# POWER.net
KiCad netlist of a schematic drawn in Altium Designer
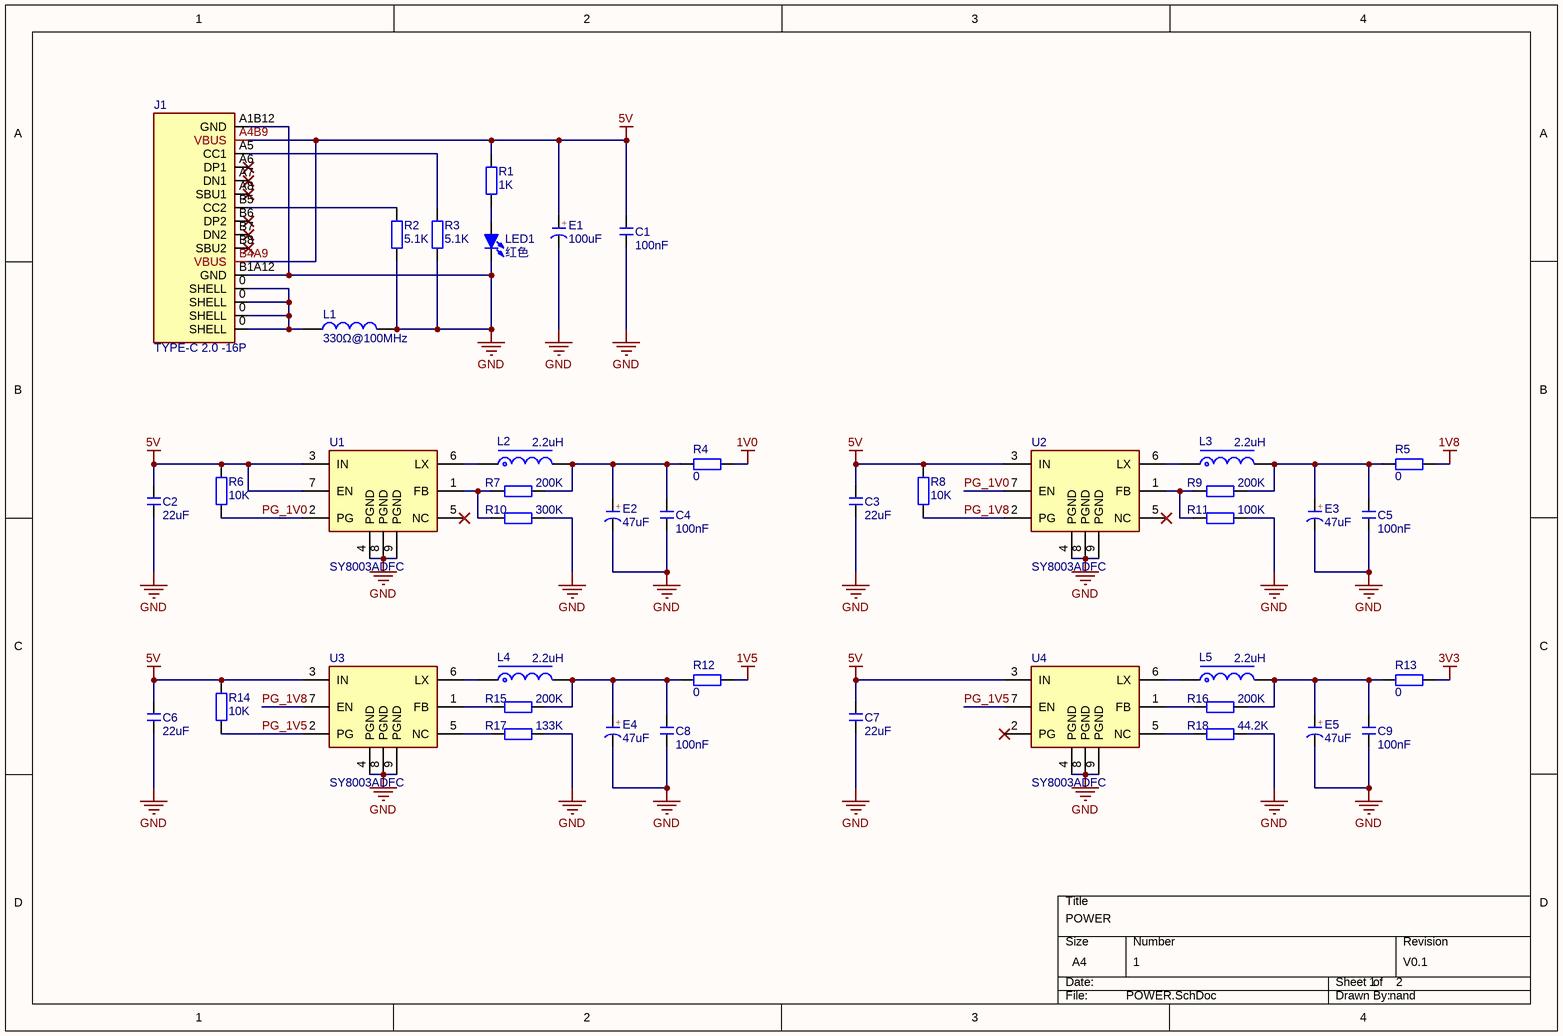
[diagram p0: POWER.SchDoc]

(export (version "E")
  (design (tool "Eeschema 10.0.6"))
  (components
    (comp (ref "C1")
      (value "100nF")
      (footprint "C 0402_L")
      (description "无极性贴片电容")
      (fields (field (name "版权归属") "源创客"))
      (libsource (lib "3.1   - 电阻-电容-电感") (part "C"))
    )
    (comp (ref "C2")
      (value "22uF")
      (footprint "C 0805_L")
      (description "无极性贴片电容")
      (fields (field (name "版权归属") "源创客"))
      (libsource (lib "3.1   - 电阻-电容-电感") (part "C"))
    )
    (comp (ref "C3")
      (value "22uF")
      (footprint "C 0805_L")
      (description "无极性贴片电容")
      (fields (field (name "版权归属") "源创客"))
      (libsource (lib "3.1   - 电阻-电容-电感") (part "C"))
    )
    (comp (ref "C4")
      (value "100nF")
      (footprint "C 0402_L")
      (description "无极性贴片电容")
      (fields (field (name "版权归属") "源创客"))
      (libsource (lib "3.1   - 电阻-电容-电感") (part "C"))
    )
    (comp (ref "C5")
      (value "100nF")
      (footprint "C 0402_L")
      (description "无极性贴片电容")
      (fields (field (name "版权归属") "源创客"))
      (libsource (lib "3.1   - 电阻-电容-电感") (part "C"))
    )
    (comp (ref "C6")
      (value "22uF")
      (footprint "C 0805_L")
      (description "无极性贴片电容")
      (fields (field (name "版权归属") "源创客"))
      (libsource (lib "3.1   - 电阻-电容-电感") (part "C"))
    )
    (comp (ref "C7")
      (value "22uF")
      (footprint "C 0805_L")
      (description "无极性贴片电容")
      (fields (field (name "版权归属") "源创客"))
      (libsource (lib "3.1   - 电阻-电容-电感") (part "C"))
    )
    (comp (ref "C8")
      (value "100nF")
      (footprint "C 0402_L")
      (description "无极性贴片电容")
      (fields (field (name "版权归属") "源创客"))
      (libsource (lib "3.1   - 电阻-电容-电感") (part "C"))
    )
    (comp (ref "C9")
      (value "100nF")
      (footprint "C 0402_L")
      (description "无极性贴片电容")
      (fields (field (name "版权归属") "源创客"))
      (libsource (lib "3.1   - 电阻-电容-电感") (part "C"))
    )
    (comp (ref "E1")
      (value "100uF")
      (footprint "CD A(3216)")
      (description "贴片钽电容")
      (fields (field (name "版权归属") "源创客"))
      (libsource (lib "3.1   - 电阻-电容-电感") (part "C-CD"))
    )
    (comp (ref "E2")
      (value "47uF")
      (footprint "CD A(3216)")
      (description "贴片钽电容")
      (fields (field (name "版权归属") "源创客"))
      (libsource (lib "3.1   - 电阻-电容-电感") (part "C-CD"))
    )
    (comp (ref "E3")
      (value "47uF")
      (footprint "CD A(3216)")
      (description "贴片钽电容")
      (fields (field (name "版权归属") "源创客"))
      (libsource (lib "3.1   - 电阻-电容-电感") (part "C-CD"))
    )
    (comp (ref "E4")
      (value "47uF")
      (footprint "CD A(3216)")
      (description "贴片钽电容")
      (fields (field (name "版权归属") "源创客"))
      (libsource (lib "3.1   - 电阻-电容-电感") (part "C-CD"))
    )
    (comp (ref "E5")
      (value "47uF")
      (footprint "CD A(3216)")
      (description "贴片钽电容")
      (fields (field (name "版权归属") "源创客"))
      (libsource (lib "3.1   - 电阻-电容-电感") (part "C-CD"))
    )
    (comp (ref "J1")
      (value "TYPE-C 2.0 -16P")
      (footprint "USB-C-SMD_16P")
      (description "USB2.0_Type-C_16Pin母座")
      (libsource (lib "4.1   - 接口类") (part "USB2.0_Type-C_16Pin"))
    )
    (comp (ref "L1")
      (value "330Ω@100MHz")
      (footprint "L 0805")
      (description "小功率贴片电感")
      (fields (field (name "版权归属") "源创客"))
      (libsource (lib "3.1   - 电阻-电容-电感") (part "L"))
    )
    (comp (ref "L2")
      (value "2.2uH")
      (footprint "CD52")
      (description "贴片功率电感")
      (fields (field (name "版权归属") "源创客"))
      (libsource (lib "3.1   - 电阻-电容-电感") (part "L-CD"))
    )
    (comp (ref "L3")
      (value "2.2uH")
      (footprint "CD52")
      (description "贴片功率电感")
      (fields (field (name "版权归属") "源创客"))
      (libsource (lib "3.1   - 电阻-电容-电感") (part "L-CD"))
    )
    (comp (ref "L4")
      (value "2.2uH")
      (footprint "CD52")
      (description "贴片功率电感")
      (fields (field (name "版权归属") "源创客"))
      (libsource (lib "3.1   - 电阻-电容-电感") (part "L-CD"))
    )
    (comp (ref "L5")
      (value "2.2uH")
      (footprint "CD52")
      (description "贴片功率电感")
      (fields (field (name "版权归属") "源创客"))
      (libsource (lib "3.1   - 电阻-电容-电感") (part "L-CD"))
    )
    (comp (ref "LED1")
      (value "红色")
      (footprint "LED 0805G")
      (description "贴片LED")
      (fields (field (name "版权归属") "源创客"))
      (libsource (lib "9.1   - LED") (part "LED-SMD"))
    )
    (comp (ref "R1")
      (value "1K")
      (footprint "R 0402_L")
      (description "贴片电阻")
      (fields (field (name "版权归属") "源创客"))
      (libsource (lib "3.1   - 电阻-电容-电感") (part "R"))
    )
    (comp (ref "R2")
      (value "5.1K")
      (footprint "R 0402_L")
      (description "贴片电阻")
      (fields (field (name "版权归属") "源创客"))
      (libsource (lib "3.1   - 电阻-电容-电感") (part "R"))
    )
    (comp (ref "R3")
      (value "5.1K")
      (footprint "R 0402_L")
      (description "贴片电阻")
      (fields (field (name "版权归属") "源创客"))
      (libsource (lib "3.1   - 电阻-电容-电感") (part "R"))
    )
    (comp (ref "R4")
      (value "0")
      (footprint "R 0603_L")
      (description "贴片电阻")
      (fields (field (name "版权归属") "源创客"))
      (libsource (lib "3.1   - 电阻-电容-电感") (part "R"))
    )
    (comp (ref "R5")
      (value "0")
      (footprint "R 0603_L")
      (description "贴片电阻")
      (fields (field (name "版权归属") "源创客"))
      (libsource (lib "3.1   - 电阻-电容-电感") (part "R"))
    )
    (comp (ref "R6")
      (value "10K")
      (footprint "R 0402_L")
      (description "贴片电阻")
      (fields (field (name "版权归属") "源创客"))
      (libsource (lib "3.1   - 电阻-电容-电感") (part "R"))
    )
    (comp (ref "R7")
      (value "200K")
      (footprint "R 0805_L")
      (description "贴片电阻")
      (fields (field (name "版权归属") "源创客"))
      (libsource (lib "3.1   - 电阻-电容-电感") (part "R"))
    )
    (comp (ref "R8")
      (value "10K")
      (footprint "R 0402_L")
      (description "贴片电阻")
      (fields (field (name "版权归属") "源创客"))
      (libsource (lib "3.1   - 电阻-电容-电感") (part "R"))
    )
    (comp (ref "R9")
      (value "200K")
      (footprint "R 0805_L")
      (description "贴片电阻")
      (fields (field (name "版权归属") "源创客"))
      (libsource (lib "3.1   - 电阻-电容-电感") (part "R"))
    )
    (comp (ref "R10")
      (value "300K")
      (footprint "R 0805_L")
      (description "贴片电阻")
      (fields (field (name "版权归属") "源创客"))
      (libsource (lib "3.1   - 电阻-电容-电感") (part "R"))
    )
    (comp (ref "R11")
      (value "100K")
      (footprint "R 0805_L")
      (description "贴片电阻")
      (fields (field (name "版权归属") "源创客"))
      (libsource (lib "3.1   - 电阻-电容-电感") (part "R"))
    )
    (comp (ref "R12")
      (value "0")
      (footprint "R 0603_L")
      (description "贴片电阻")
      (fields (field (name "版权归属") "源创客"))
      (libsource (lib "3.1   - 电阻-电容-电感") (part "R"))
    )
    (comp (ref "R13")
      (value "0")
      (footprint "R 0603_L")
      (description "贴片电阻")
      (fields (field (name "版权归属") "源创客"))
      (libsource (lib "3.1   - 电阻-电容-电感") (part "R"))
    )
    (comp (ref "R14")
      (value "10K")
      (footprint "R 0402_L")
      (description "贴片电阻")
      (fields (field (name "版权归属") "源创客"))
      (libsource (lib "3.1   - 电阻-电容-电感") (part "R"))
    )
    (comp (ref "R15")
      (value "200K")
      (footprint "R 0805_L")
      (description "贴片电阻")
      (fields (field (name "版权归属") "源创客"))
      (libsource (lib "3.1   - 电阻-电容-电感") (part "R"))
    )
    (comp (ref "R16")
      (value "200K")
      (footprint "R 0805_L")
      (description "贴片电阻")
      (fields (field (name "版权归属") "源创客"))
      (libsource (lib "3.1   - 电阻-电容-电感") (part "R"))
    )
    (comp (ref "R17")
      (value "133K")
      (footprint "R 0805_L")
      (description "贴片电阻")
      (fields (field (name "版权归属") "源创客"))
      (libsource (lib "3.1   - 电阻-电容-电感") (part "R"))
    )
    (comp (ref "R18")
      (value "44.2K")
      (footprint "R 0805_L")
      (description "贴片电阻")
      (fields (field (name "版权归属") "源创客"))
      (libsource (lib "3.1   - 电阻-电容-电感") (part "R"))
    )
    (comp (ref "U1")
      (value "SY8003ADFC")
      (footprint "SON50P200X200X65-9N")
      (description "开关电源")
      (libsource (lib "1.1   - IC芯片") (part "SY8003ADFC"))
    )
    (comp (ref "U2")
      (value "SY8003ADFC")
      (footprint "SON50P200X200X65-9N")
      (description "开关电源")
      (libsource (lib "1.1   - IC芯片") (part "SY8003ADFC"))
    )
    (comp (ref "U3")
      (value "SY8003ADFC")
      (footprint "SON50P200X200X65-9N")
      (description "开关电源")
      (libsource (lib "1.1   - IC芯片") (part "SY8003ADFC"))
    )
    (comp (ref "U4")
      (value "SY8003ADFC")
      (footprint "SON50P200X200X65-9N")
      (description "开关电源")
      (libsource (lib "1.1   - IC芯片") (part "SY8003ADFC"))
    )
  )
  (nets
    (net (code "1") (name "/PG_1V0") (class "Default")
      (node (ref "R6") (pin "1") (pinfunction "1_1") (pintype "passive"))
      (node (ref "U1") (pin "2") (pinfunction "PG_2") (pintype "passive"))
      (node (ref "U2") (pin "7") (pinfunction "EN_7") (pintype "passive"))
    )
    (net (code "2") (name "/PG_1V5") (class "Default")
      (node (ref "R14") (pin "1") (pinfunction "1_1") (pintype "passive"))
      (node (ref "U3") (pin "2") (pinfunction "PG_2") (pintype "passive"))
      (node (ref "U4") (pin "7") (pinfunction "EN_7") (pintype "passive"))
    )
    (net (code "3") (name "/PG_1V8") (class "Default")
      (node (ref "R8") (pin "1") (pinfunction "1_1") (pintype "passive"))
      (node (ref "U2") (pin "2") (pinfunction "PG_2") (pintype "passive"))
      (node (ref "U3") (pin "7") (pinfunction "EN_7") (pintype "passive"))
    )
    (net (code "4") (name "1V0") (class "Default")
      (node (ref "R4") (pin "1") (pinfunction "1_1") (pintype "passive"))
    )
    (net (code "5") (name "1V5") (class "Default")
      (node (ref "R12") (pin "1") (pinfunction "1_1") (pintype "passive"))
    )
    (net (code "6") (name "1V8") (class "Default")
      (node (ref "R5") (pin "1") (pinfunction "1_1") (pintype "passive"))
    )
    (net (code "7") (name "3V3") (class "Default")
      (node (ref "R13") (pin "1") (pinfunction "1_1") (pintype "passive"))
    )
    (net (code "8") (name "5V") (class "Default")
      (node (ref "C1") (pin "2") (pinfunction "2_2") (pintype "passive"))
      (node (ref "C2") (pin "2") (pinfunction "2_2") (pintype "passive"))
      (node (ref "C3") (pin "2") (pinfunction "2_2") (pintype "passive"))
      (node (ref "C6") (pin "2") (pinfunction "2_2") (pintype "passive"))
      (node (ref "C7") (pin "2") (pinfunction "2_2") (pintype "passive"))
      (node (ref "E1") (pin "1") (pinfunction "A_1") (pintype "passive"))
      (node (ref "J1") (pin "A4B9") (pinfunction "VBUS_A4B9") (pintype "passive"))
      (node (ref "J1") (pin "B4A9") (pinfunction "VBUS_B4A9") (pintype "passive"))
      (node (ref "R1") (pin "2") (pinfunction "2_2") (pintype "passive"))
      (node (ref "R14") (pin "2") (pinfunction "2_2") (pintype "passive"))
      (node (ref "R6") (pin "2") (pinfunction "2_2") (pintype "passive"))
      (node (ref "R8") (pin "2") (pinfunction "2_2") (pintype "passive"))
      (node (ref "U1") (pin "3") (pinfunction "IN_3") (pintype "passive"))
      (node (ref "U1") (pin "7") (pinfunction "EN_7") (pintype "passive"))
      (node (ref "U2") (pin "3") (pinfunction "IN_3") (pintype "passive"))
      (node (ref "U3") (pin "3") (pinfunction "IN_3") (pintype "passive"))
      (node (ref "U4") (pin "3") (pinfunction "IN_3") (pintype "passive"))
    )
    (net (code "9") (name "GND") (class "Default")
      (node (ref "C1") (pin "1") (pinfunction "1_1") (pintype "passive"))
      (node (ref "C2") (pin "1") (pinfunction "1_1") (pintype "passive"))
      (node (ref "C3") (pin "1") (pinfunction "1_1") (pintype "passive"))
      (node (ref "C4") (pin "1") (pinfunction "1_1") (pintype "passive"))
      (node (ref "C5") (pin "1") (pinfunction "1_1") (pintype "passive"))
      (node (ref "C6") (pin "1") (pinfunction "1_1") (pintype "passive"))
      (node (ref "C7") (pin "1") (pinfunction "1_1") (pintype "passive"))
      (node (ref "C8") (pin "1") (pinfunction "1_1") (pintype "passive"))
      (node (ref "C9") (pin "1") (pinfunction "1_1") (pintype "passive"))
      (node (ref "E1") (pin "2") (pinfunction "K_2") (pintype "passive"))
      (node (ref "E2") (pin "2") (pinfunction "K_2") (pintype "passive"))
      (node (ref "E3") (pin "2") (pinfunction "K_2") (pintype "passive"))
      (node (ref "E4") (pin "2") (pinfunction "K_2") (pintype "passive"))
      (node (ref "E5") (pin "2") (pinfunction "K_2") (pintype "passive"))
      (node (ref "J1") (pin "A1B12") (pinfunction "GND_A1B12") (pintype "passive"))
      (node (ref "J1") (pin "B1A12") (pinfunction "GND_B1A12") (pintype "passive"))
      (node (ref "L1") (pin "2") (pinfunction "2_2") (pintype "passive"))
      (node (ref "LED1") (pin "2") (pinfunction "K_2") (pintype "passive"))
      (node (ref "R10") (pin "1") (pinfunction "1_1") (pintype "passive"))
      (node (ref "R11") (pin "1") (pinfunction "1_1") (pintype "passive"))
      (node (ref "R17") (pin "1") (pinfunction "1_1") (pintype "passive"))
      (node (ref "R18") (pin "1") (pinfunction "1_1") (pintype "passive"))
      (node (ref "R2") (pin "1") (pinfunction "1_1") (pintype "passive"))
      (node (ref "R3") (pin "1") (pinfunction "1_1") (pintype "passive"))
      (node (ref "U1") (pin "4") (pinfunction "PGND_4") (pintype "passive"))
      (node (ref "U1") (pin "8") (pinfunction "PGND_8") (pintype "passive"))
      (node (ref "U1") (pin "9") (pinfunction "PGND_9") (pintype "passive"))
      (node (ref "U2") (pin "4") (pinfunction "PGND_4") (pintype "passive"))
      (node (ref "U2") (pin "8") (pinfunction "PGND_8") (pintype "passive"))
      (node (ref "U2") (pin "9") (pinfunction "PGND_9") (pintype "passive"))
      (node (ref "U3") (pin "4") (pinfunction "PGND_4") (pintype "passive"))
      (node (ref "U3") (pin "8") (pinfunction "PGND_8") (pintype "passive"))
      (node (ref "U3") (pin "9") (pinfunction "PGND_9") (pintype "passive"))
      (node (ref "U4") (pin "4") (pinfunction "PGND_4") (pintype "passive"))
      (node (ref "U4") (pin "8") (pinfunction "PGND_8") (pintype "passive"))
      (node (ref "U4") (pin "9") (pinfunction "PGND_9") (pintype "passive"))
    )
    (net (code "10") (name "Net-(E2-A)") (class "Default")
      (node (ref "C4") (pin "2") (pinfunction "2_2") (pintype "passive"))
      (node (ref "E2") (pin "1") (pinfunction "A_1") (pintype "passive"))
      (node (ref "L2") (pin "2") (pinfunction "2_2") (pintype "passive"))
      (node (ref "R4") (pin "2") (pinfunction "2_2") (pintype "passive"))
      (node (ref "R7") (pin "1") (pinfunction "1_1") (pintype "passive"))
    )
    (net (code "11") (name "Net-(E3-A)") (class "Default")
      (node (ref "C5") (pin "2") (pinfunction "2_2") (pintype "passive"))
      (node (ref "E3") (pin "1") (pinfunction "A_1") (pintype "passive"))
      (node (ref "L3") (pin "2") (pinfunction "2_2") (pintype "passive"))
      (node (ref "R5") (pin "2") (pinfunction "2_2") (pintype "passive"))
      (node (ref "R9") (pin "1") (pinfunction "1_1") (pintype "passive"))
    )
    (net (code "12") (name "Net-(E4-A)") (class "Default")
      (node (ref "C8") (pin "2") (pinfunction "2_2") (pintype "passive"))
      (node (ref "E4") (pin "1") (pinfunction "A_1") (pintype "passive"))
      (node (ref "L4") (pin "2") (pinfunction "2_2") (pintype "passive"))
      (node (ref "R12") (pin "2") (pinfunction "2_2") (pintype "passive"))
      (node (ref "R15") (pin "1") (pinfunction "1_1") (pintype "passive"))
    )
    (net (code "13") (name "Net-(E5-A)") (class "Default")
      (node (ref "C9") (pin "2") (pinfunction "2_2") (pintype "passive"))
      (node (ref "E5") (pin "1") (pinfunction "A_1") (pintype "passive"))
      (node (ref "L5") (pin "2") (pinfunction "2_2") (pintype "passive"))
      (node (ref "R13") (pin "2") (pinfunction "2_2") (pintype "passive"))
      (node (ref "R16") (pin "1") (pinfunction "1_1") (pintype "passive"))
    )
    (net (code "14") (name "Net-(J1-CC1)") (class "Default")
      (node (ref "J1") (pin "A5") (pinfunction "CC1_A5") (pintype "passive"))
      (node (ref "R3") (pin "2") (pinfunction "2_2") (pintype "passive"))
    )
    (net (code "15") (name "Net-(J1-CC2)") (class "Default")
      (node (ref "J1") (pin "B5") (pinfunction "CC2_B5") (pintype "passive"))
      (node (ref "R2") (pin "2") (pinfunction "2_2") (pintype "passive"))
    )
    (net (code "16") (name "Net-(J1-SHELL)") (class "Default")
      (node (ref "J1") (pin "0") (pinfunction "SHELL_0") (pintype "passive"))
      (node (ref "L1") (pin "1") (pinfunction "1_1") (pintype "passive"))
    )
    (net (code "17") (name "Net-(LED1-A)") (class "Default")
      (node (ref "LED1") (pin "1") (pinfunction "A_1") (pintype "passive"))
      (node (ref "R1") (pin "1") (pinfunction "1_1") (pintype "passive"))
    )
    (net (code "18") (name "Net-(U1-FB)") (class "Default")
      (node (ref "R10") (pin "2") (pinfunction "2_2") (pintype "passive"))
      (node (ref "R7") (pin "2") (pinfunction "2_2") (pintype "passive"))
      (node (ref "U1") (pin "1") (pinfunction "FB_1") (pintype "passive"))
    )
    (net (code "19") (name "Net-(U1-LX)") (class "Default")
      (node (ref "L2") (pin "1") (pinfunction "1_1") (pintype "passive"))
      (node (ref "U1") (pin "6") (pinfunction "LX_6") (pintype "passive"))
    )
    (net (code "20") (name "Net-(U2-FB)") (class "Default")
      (node (ref "R11") (pin "2") (pinfunction "2_2") (pintype "passive"))
      (node (ref "R9") (pin "2") (pinfunction "2_2") (pintype "passive"))
      (node (ref "U2") (pin "1") (pinfunction "FB_1") (pintype "passive"))
    )
    (net (code "21") (name "Net-(U2-LX)") (class "Default")
      (node (ref "L3") (pin "1") (pinfunction "1_1") (pintype "passive"))
      (node (ref "U2") (pin "6") (pinfunction "LX_6") (pintype "passive"))
    )
    (net (code "22") (name "Net-(U3-FB)") (class "Default")
      (node (ref "R15") (pin "2") (pinfunction "2_2") (pintype "passive"))
      (node (ref "U3") (pin "1") (pinfunction "FB_1") (pintype "passive"))
    )
    (net (code "23") (name "Net-(U3-LX)") (class "Default")
      (node (ref "L4") (pin "1") (pinfunction "1_1") (pintype "passive"))
      (node (ref "U3") (pin "6") (pinfunction "LX_6") (pintype "passive"))
    )
    (net (code "24") (name "Net-(U3-NC)") (class "Default")
      (node (ref "R17") (pin "2") (pinfunction "2_2") (pintype "passive"))
      (node (ref "U3") (pin "5") (pinfunction "NC_5") (pintype "passive"))
    )
    (net (code "25") (name "Net-(U4-FB)") (class "Default")
      (node (ref "R16") (pin "2") (pinfunction "2_2") (pintype "passive"))
      (node (ref "U4") (pin "1") (pinfunction "FB_1") (pintype "passive"))
    )
    (net (code "26") (name "Net-(U4-LX)") (class "Default")
      (node (ref "L5") (pin "1") (pinfunction "1_1") (pintype "passive"))
      (node (ref "U4") (pin "6") (pinfunction "LX_6") (pintype "passive"))
    )
    (net (code "27") (name "Net-(U4-NC)") (class "Default")
      (node (ref "R18") (pin "2") (pinfunction "2_2") (pintype "passive"))
      (node (ref "U4") (pin "5") (pinfunction "NC_5") (pintype "passive"))
    )
    (net (code "28") (name "unconnected-(J1-DN1-PadA7)") (class "Default")
      (node (ref "J1") (pin "A7") (pinfunction "DN1_A7") (pintype "passive+no_connect"))
    )
    (net (code "29") (name "unconnected-(J1-DN2-PadB7)") (class "Default")
      (node (ref "J1") (pin "B7") (pinfunction "DN2_B7") (pintype "passive+no_connect"))
    )
    (net (code "30") (name "unconnected-(J1-DP1-PadA6)") (class "Default")
      (node (ref "J1") (pin "A6") (pinfunction "DP1_A6") (pintype "passive+no_connect"))
    )
    (net (code "31") (name "unconnected-(J1-DP2-PadB6)") (class "Default")
      (node (ref "J1") (pin "B6") (pinfunction "DP2_B6") (pintype "passive+no_connect"))
    )
    (net (code "32") (name "unconnected-(J1-SBU1-PadA8)") (class "Default")
      (node (ref "J1") (pin "A8") (pinfunction "SBU1_A8") (pintype "passive+no_connect"))
    )
    (net (code "33") (name "unconnected-(J1-SBU2-PadB8)") (class "Default")
      (node (ref "J1") (pin "B8") (pinfunction "SBU2_B8") (pintype "passive+no_connect"))
    )
    (net (code "34") (name "unconnected-(U1-NC-Pad5)") (class "Default")
      (node (ref "U1") (pin "5") (pinfunction "NC_5") (pintype "passive+no_connect"))
    )
    (net (code "35") (name "unconnected-(U2-NC-Pad5)") (class "Default")
      (node (ref "U2") (pin "5") (pinfunction "NC_5") (pintype "passive+no_connect"))
    )
    (net (code "36") (name "unconnected-(U4-PG-Pad2)") (class "Default")
      (node (ref "U4") (pin "2") (pinfunction "PG_2") (pintype "passive+no_connect"))
    )
  )
)
